# Sheet1.net
KiCad netlist of a schematic drawn in Altium Designer
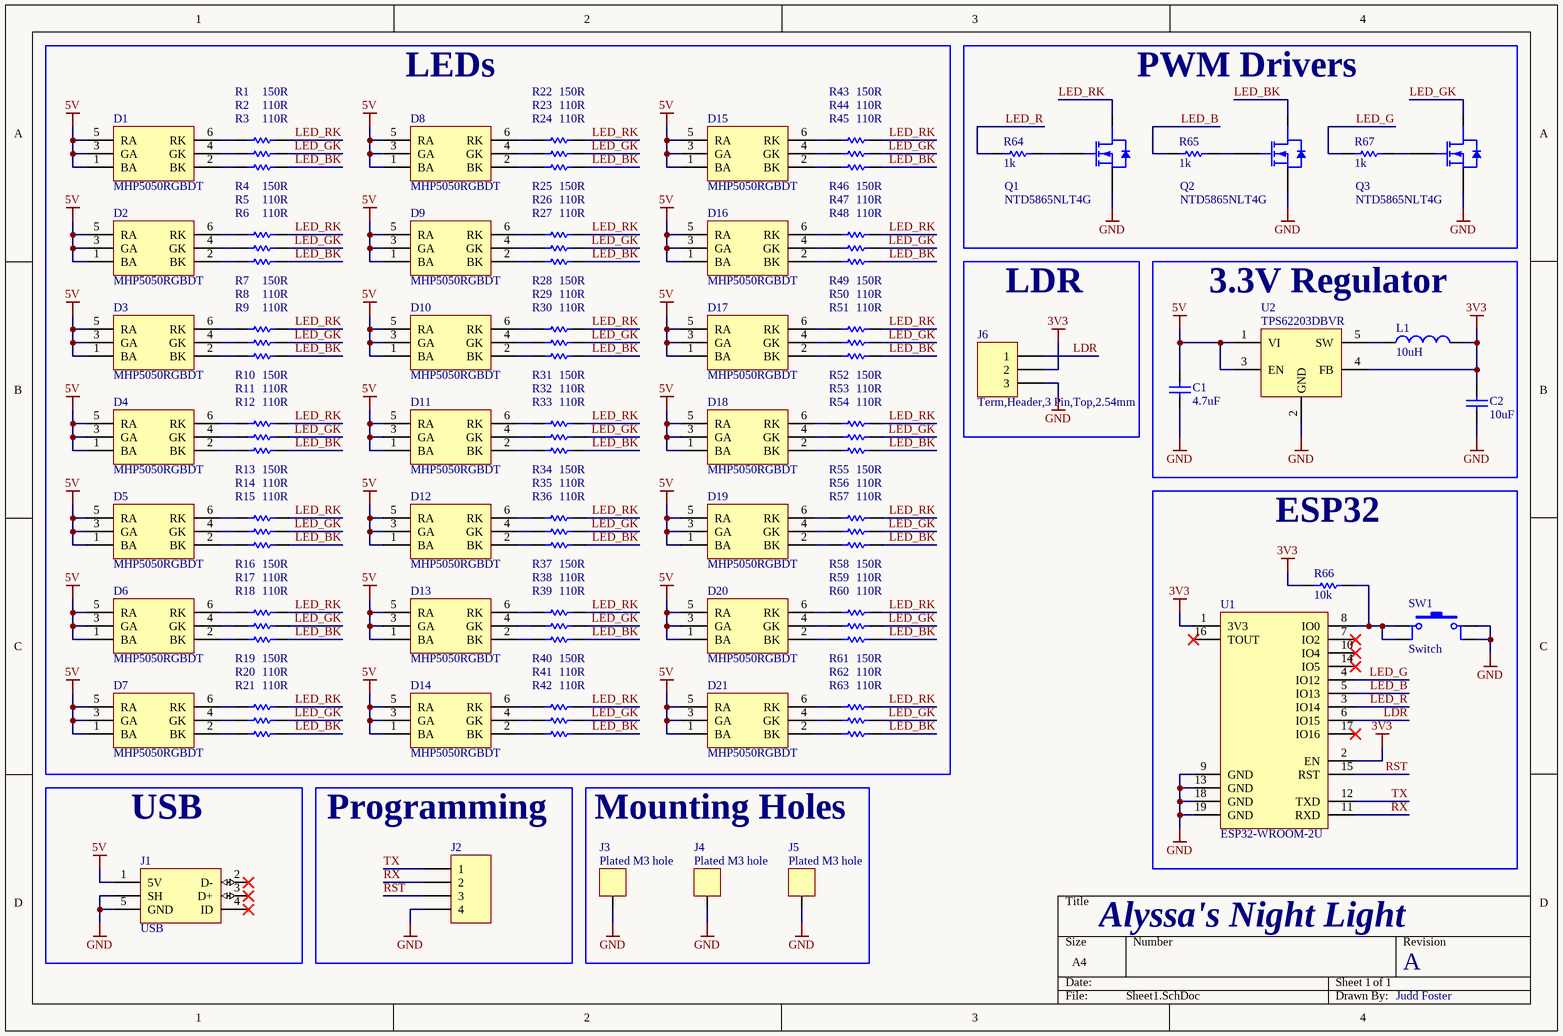
[diagram p0: Sheet1.SchDoc]

(export (version "E")
  (design (tool "Eeschema 10.0.6"))
  (components
    (comp (ref "C1")
      (value "4.7uF")
      (footprint "Cap,SMD,0805")
      (description "4.7µF ±10% 16V Ceramic Capacitor X7R 0805 (2012 Metric)")
      (fields
        (field (name "VENDOR PART NUMBER") "490-14466-1-ND")
        (field (name "MANUFACTURER") "KEMET")
        (field (name "CREATEDBY") "Judd Foster")
      )
      (libsource (lib "symbols") (part "CAP,Cer,4.7uF,16VDC,X7R,0805"))
    )
    (comp (ref "C2")
      (value "10uF")
      (footprint "Cap,SMD,0805")
      (description "CAP CER 10UF 10V X5R 0805")
      (fields
        (field (name "VENDOR PART NUMBER") "399-4925-1-ND")
        (field (name "MANUFACTURER") "KEMET")
        (field (name "CREATEDBY") "Judd Foster")
      )
      (libsource (lib "symbols") (part "CAP,Cer,10uF,10VDC,X5R,0805"))
    )
    (comp (ref "D1")
      (value "MHP5050RGBDT")
      (footprint "LED,RGB,SMD,5050")
      (description "SMD,5x5mm Light Emitting Diodes (LED) RoHS")
      (fields
        (field (name "MANUFACTURER") "MEIHUA")
        (field (name "VENDOR PART NUMBER") "C409780")
        (field (name "CREATEDBY") "Judd Foster")
      )
      (libsource (lib "symbols") (part "LED,Tri-Color,RGB,SMD,5050"))
    )
    (comp (ref "D2")
      (value "MHP5050RGBDT")
      (footprint "LED,RGB,SMD,5050")
      (description "SMD,5x5mm Light Emitting Diodes (LED) RoHS")
      (fields
        (field (name "MANUFACTURER") "MEIHUA")
        (field (name "VENDOR PART NUMBER") "C409780")
        (field (name "CREATEDBY") "Judd Foster")
      )
      (libsource (lib "symbols") (part "LED,Tri-Color,RGB,SMD,5050"))
    )
    (comp (ref "D3")
      (value "MHP5050RGBDT")
      (footprint "LED,RGB,SMD,5050")
      (description "SMD,5x5mm Light Emitting Diodes (LED) RoHS")
      (fields
        (field (name "MANUFACTURER") "MEIHUA")
        (field (name "VENDOR PART NUMBER") "C409780")
        (field (name "CREATEDBY") "Judd Foster")
      )
      (libsource (lib "symbols") (part "LED,Tri-Color,RGB,SMD,5050"))
    )
    (comp (ref "D4")
      (value "MHP5050RGBDT")
      (footprint "LED,RGB,SMD,5050")
      (description "SMD,5x5mm Light Emitting Diodes (LED) RoHS")
      (fields
        (field (name "MANUFACTURER") "MEIHUA")
        (field (name "VENDOR PART NUMBER") "C409780")
        (field (name "CREATEDBY") "Judd Foster")
      )
      (libsource (lib "symbols") (part "LED,Tri-Color,RGB,SMD,5050"))
    )
    (comp (ref "D5")
      (value "MHP5050RGBDT")
      (footprint "LED,RGB,SMD,5050")
      (description "SMD,5x5mm Light Emitting Diodes (LED) RoHS")
      (fields
        (field (name "MANUFACTURER") "MEIHUA")
        (field (name "VENDOR PART NUMBER") "C409780")
        (field (name "CREATEDBY") "Judd Foster")
      )
      (libsource (lib "symbols") (part "LED,Tri-Color,RGB,SMD,5050"))
    )
    (comp (ref "D6")
      (value "MHP5050RGBDT")
      (footprint "LED,RGB,SMD,5050")
      (description "SMD,5x5mm Light Emitting Diodes (LED) RoHS")
      (fields
        (field (name "MANUFACTURER") "MEIHUA")
        (field (name "VENDOR PART NUMBER") "C409780")
        (field (name "CREATEDBY") "Judd Foster")
      )
      (libsource (lib "symbols") (part "LED,Tri-Color,RGB,SMD,5050"))
    )
    (comp (ref "D7")
      (value "MHP5050RGBDT")
      (footprint "LED,RGB,SMD,5050")
      (description "SMD,5x5mm Light Emitting Diodes (LED) RoHS")
      (fields
        (field (name "MANUFACTURER") "MEIHUA")
        (field (name "VENDOR PART NUMBER") "C409780")
        (field (name "CREATEDBY") "Judd Foster")
      )
      (libsource (lib "symbols") (part "LED,Tri-Color,RGB,SMD,5050"))
    )
    (comp (ref "D8")
      (value "MHP5050RGBDT")
      (footprint "LED,RGB,SMD,5050")
      (description "SMD,5x5mm Light Emitting Diodes (LED) RoHS")
      (fields
        (field (name "MANUFACTURER") "MEIHUA")
        (field (name "VENDOR PART NUMBER") "C409780")
        (field (name "CREATEDBY") "Judd Foster")
      )
      (libsource (lib "symbols") (part "LED,Tri-Color,RGB,SMD,5050"))
    )
    (comp (ref "D9")
      (value "MHP5050RGBDT")
      (footprint "LED,RGB,SMD,5050")
      (description "SMD,5x5mm Light Emitting Diodes (LED) RoHS")
      (fields
        (field (name "MANUFACTURER") "MEIHUA")
        (field (name "VENDOR PART NUMBER") "C409780")
        (field (name "CREATEDBY") "Judd Foster")
      )
      (libsource (lib "symbols") (part "LED,Tri-Color,RGB,SMD,5050"))
    )
    (comp (ref "D10")
      (value "MHP5050RGBDT")
      (footprint "LED,RGB,SMD,5050")
      (description "SMD,5x5mm Light Emitting Diodes (LED) RoHS")
      (fields
        (field (name "MANUFACTURER") "MEIHUA")
        (field (name "VENDOR PART NUMBER") "C409780")
        (field (name "CREATEDBY") "Judd Foster")
      )
      (libsource (lib "symbols") (part "LED,Tri-Color,RGB,SMD,5050"))
    )
    (comp (ref "D11")
      (value "MHP5050RGBDT")
      (footprint "LED,RGB,SMD,5050")
      (description "SMD,5x5mm Light Emitting Diodes (LED) RoHS")
      (fields
        (field (name "MANUFACTURER") "MEIHUA")
        (field (name "VENDOR PART NUMBER") "C409780")
        (field (name "CREATEDBY") "Judd Foster")
      )
      (libsource (lib "symbols") (part "LED,Tri-Color,RGB,SMD,5050"))
    )
    (comp (ref "D12")
      (value "MHP5050RGBDT")
      (footprint "LED,RGB,SMD,5050")
      (description "SMD,5x5mm Light Emitting Diodes (LED) RoHS")
      (fields
        (field (name "MANUFACTURER") "MEIHUA")
        (field (name "VENDOR PART NUMBER") "C409780")
        (field (name "CREATEDBY") "Judd Foster")
      )
      (libsource (lib "symbols") (part "LED,Tri-Color,RGB,SMD,5050"))
    )
    (comp (ref "D13")
      (value "MHP5050RGBDT")
      (footprint "LED,RGB,SMD,5050")
      (description "SMD,5x5mm Light Emitting Diodes (LED) RoHS")
      (fields
        (field (name "MANUFACTURER") "MEIHUA")
        (field (name "VENDOR PART NUMBER") "C409780")
        (field (name "CREATEDBY") "Judd Foster")
      )
      (libsource (lib "symbols") (part "LED,Tri-Color,RGB,SMD,5050"))
    )
    (comp (ref "D14")
      (value "MHP5050RGBDT")
      (footprint "LED,RGB,SMD,5050")
      (description "SMD,5x5mm Light Emitting Diodes (LED) RoHS")
      (fields
        (field (name "MANUFACTURER") "MEIHUA")
        (field (name "VENDOR PART NUMBER") "C409780")
        (field (name "CREATEDBY") "Judd Foster")
      )
      (libsource (lib "symbols") (part "LED,Tri-Color,RGB,SMD,5050"))
    )
    (comp (ref "D15")
      (value "MHP5050RGBDT")
      (footprint "LED,RGB,SMD,5050")
      (description "SMD,5x5mm Light Emitting Diodes (LED) RoHS")
      (fields
        (field (name "MANUFACTURER") "MEIHUA")
        (field (name "VENDOR PART NUMBER") "C409780")
        (field (name "CREATEDBY") "Judd Foster")
      )
      (libsource (lib "symbols") (part "LED,Tri-Color,RGB,SMD,5050"))
    )
    (comp (ref "D16")
      (value "MHP5050RGBDT")
      (footprint "LED,RGB,SMD,5050")
      (description "SMD,5x5mm Light Emitting Diodes (LED) RoHS")
      (fields
        (field (name "MANUFACTURER") "MEIHUA")
        (field (name "VENDOR PART NUMBER") "C409780")
        (field (name "CREATEDBY") "Judd Foster")
      )
      (libsource (lib "symbols") (part "LED,Tri-Color,RGB,SMD,5050"))
    )
    (comp (ref "D17")
      (value "MHP5050RGBDT")
      (footprint "LED,RGB,SMD,5050")
      (description "SMD,5x5mm Light Emitting Diodes (LED) RoHS")
      (fields
        (field (name "MANUFACTURER") "MEIHUA")
        (field (name "VENDOR PART NUMBER") "C409780")
        (field (name "CREATEDBY") "Judd Foster")
      )
      (libsource (lib "symbols") (part "LED,Tri-Color,RGB,SMD,5050"))
    )
    (comp (ref "D18")
      (value "MHP5050RGBDT")
      (footprint "LED,RGB,SMD,5050")
      (description "SMD,5x5mm Light Emitting Diodes (LED) RoHS")
      (fields
        (field (name "MANUFACTURER") "MEIHUA")
        (field (name "VENDOR PART NUMBER") "C409780")
        (field (name "CREATEDBY") "Judd Foster")
      )
      (libsource (lib "symbols") (part "LED,Tri-Color,RGB,SMD,5050"))
    )
    (comp (ref "D19")
      (value "MHP5050RGBDT")
      (footprint "LED,RGB,SMD,5050")
      (description "SMD,5x5mm Light Emitting Diodes (LED) RoHS")
      (fields
        (field (name "MANUFACTURER") "MEIHUA")
        (field (name "VENDOR PART NUMBER") "C409780")
        (field (name "CREATEDBY") "Judd Foster")
      )
      (libsource (lib "symbols") (part "LED,Tri-Color,RGB,SMD,5050"))
    )
    (comp (ref "D20")
      (value "MHP5050RGBDT")
      (footprint "LED,RGB,SMD,5050")
      (description "SMD,5x5mm Light Emitting Diodes (LED) RoHS")
      (fields
        (field (name "MANUFACTURER") "MEIHUA")
        (field (name "VENDOR PART NUMBER") "C409780")
        (field (name "CREATEDBY") "Judd Foster")
      )
      (libsource (lib "symbols") (part "LED,Tri-Color,RGB,SMD,5050"))
    )
    (comp (ref "D21")
      (value "MHP5050RGBDT")
      (footprint "LED,RGB,SMD,5050")
      (description "SMD,5x5mm Light Emitting Diodes (LED) RoHS")
      (fields
        (field (name "MANUFACTURER") "MEIHUA")
        (field (name "VENDOR PART NUMBER") "C409780")
        (field (name "CREATEDBY") "Judd Foster")
      )
      (libsource (lib "symbols") (part "LED,Tri-Color,RGB,SMD,5050"))
    )
    (comp (ref "J1")
      (value "USB")
      (footprint "Conn,USB,MicroB,SMD")
      (description "USB - micro B USB 2.0 Receptacle Connector 5 Position Surface Mount, Right Angle; Through Hole")
      (fields
        (field (name "MANUFACTURER") "Amphenol ICC (FCI)")
        (field (name "MANUFACTURER PART NUMBER") "10118193-0001LF")
        (field (name "CREATEDBY") "Judd Foster")
      )
      (libsource (lib "symbols") (part "Conn,USB.Micro_B,SMD"))
    )
    (comp (ref "J2")
      (value "Term,Header,4 Pin,Top,2.54mm")
      (footprint "Term,Header,4Pin,2.54mm")
      (description "Connector Header Through Hole 4 position 0.100\" (2.54mm)")
      (fields
        (field (name "VENDOR PART NUMBER") "609-10082627-404HLF-ND")
        (field (name "MANUFACTURER") "Amphenol ICC (FCI)")
        (field (name "CREATED BY") "Judd Foster")
      )
      (libsource (lib "symbols") (part "Term,Header,4 Pin,Top,2.54mm"))
    )
    (comp (ref "J3")
      (value "Plated M3 hole")
      (footprint "HOLE,M3,3mm,PLATED")
      (description "3.5mm Drill, 7.4mm Pad, PTH")
      (fields (field (name "CREATEDBY") "Judd Foster"))
      (libsource (lib "symbols") (part "Mech,Hole,M3,3mm,Plated"))
    )
    (comp (ref "J4")
      (value "Plated M3 hole")
      (footprint "HOLE,M3,3mm,PLATED")
      (description "3.5mm Drill, 7.4mm Pad, PTH")
      (fields (field (name "CREATEDBY") "Judd Foster"))
      (libsource (lib "symbols") (part "Mech,Hole,M3,3mm,Plated"))
    )
    (comp (ref "J5")
      (value "Plated M3 hole")
      (footprint "HOLE,M3,3mm,PLATED")
      (description "3.5mm Drill, 7.4mm Pad, PTH")
      (fields (field (name "CREATEDBY") "Judd Foster"))
      (libsource (lib "symbols") (part "Mech,Hole,M3,3mm,Plated"))
    )
    (comp (ref "J6")
      (value "Term,Header,3 Pin,Top,2.54mm")
      (footprint "Term,Header,3Pin,2.54mm")
      (description "CONN HEADER VERT 3POS 2.54MM")
      (fields
        (field (name "VENDOR PART NUMBER") "732-5316-ND")
        (field (name "MANUFACTURER") "Würth Elektronik")
        (field (name "CREATED BY") "Judd Foster")
      )
      (libsource (lib "symbols") (part "Term,Header,3 Pin,Top,2.54mm"))
    )
    (comp (ref "L1")
      (value "10uH")
      (footprint "IND,Wirewound,4x4,SMD")
      (description "FIXED IND 10UH 1.17A 160 MOHM")
      (fields
        (field (name "VENDOR PART NUMBER") "‎490-5330-1-ND‎")
        (field (name "MANUFACTURER") "Murata Electronics")
        (field (name "CREATEDBY") "Judd Foster")
      )
      (libsource (lib "symbols") (part "IND,10uH,1.17A,Wirewound,SMD"))
    )
    (comp (ref "Q1")
      (value "NTD5865NLT4G")
      (footprint "DPAK3 (TO-252 3 Lead)")
      (description "MOSFET N-CH 60V 46A DPAK")
      (fields
        (field (name "MANUFACTURER") "ON Semiconductor")
        (field (name "VENDOR PART NUMBER") "NTD5865NLT4GOSCT-ND")
        (field (name "CREATEDBY") "Judd Foster")
      )
      (libsource (lib "symbols") (part "MOSFET,N Ch,60V,46A"))
    )
    (comp (ref "Q2")
      (value "NTD5865NLT4G")
      (footprint "DPAK3 (TO-252 3 Lead)")
      (description "MOSFET N-CH 60V 46A DPAK")
      (fields
        (field (name "MANUFACTURER") "ON Semiconductor")
        (field (name "VENDOR PART NUMBER") "NTD5865NLT4GOSCT-ND")
        (field (name "CREATEDBY") "Judd Foster")
      )
      (libsource (lib "symbols") (part "MOSFET,N Ch,60V,46A"))
    )
    (comp (ref "Q3")
      (value "NTD5865NLT4G")
      (footprint "DPAK3 (TO-252 3 Lead)")
      (description "MOSFET N-CH 60V 46A DPAK")
      (fields
        (field (name "MANUFACTURER") "ON Semiconductor")
        (field (name "VENDOR PART NUMBER") "NTD5865NLT4GOSCT-ND")
        (field (name "CREATEDBY") "Judd Foster")
      )
      (libsource (lib "symbols") (part "MOSFET,N Ch,60V,46A"))
    )
    (comp (ref "R1")
      (value "150R")
      (footprint "RES,0603")
      (fields
        (field (name "MANUFACTURER") "TE Connectivity Passive Product")
        (field (name "MANUFACTURER PART NUMBER") "CRGCQ0603F150R")
        (field (name "VENDOR PART NUMBER") "A129678CT-ND")
        (field (name "CREATEDBY") "Judd Foster")
      )
      (libsource (lib "symbols") (part "RES,150R,1%,0.1W,0603"))
    )
    (comp (ref "R2")
      (value "110R")
      (footprint "RES,0603")
      (description "110 Ohms ±0.5% 0.063W, 1/16W Chip Resistor 0603 (1608 Metric)  Thin Film")
      (fields
        (field (name "MANUFACTURER") "Susumu")
        (field (name "MANUFACTURER PART NUMBER") "RR0816P-111-D")
        (field (name "CREATEDBY") "Judd Foster")
      )
      (libsource (lib "symbols") (part "RES,110R,1%,0.1W,0603"))
    )
    (comp (ref "R3")
      (value "110R")
      (footprint "RES,0603")
      (description "110 Ohms ±0.5% 0.063W, 1/16W Chip Resistor 0603 (1608 Metric)  Thin Film")
      (fields
        (field (name "MANUFACTURER") "Susumu")
        (field (name "MANUFACTURER PART NUMBER") "RR0816P-111-D")
        (field (name "CREATEDBY") "Judd Foster")
      )
      (libsource (lib "symbols") (part "RES,110R,1%,0.1W,0603"))
    )
    (comp (ref "R4")
      (value "150R")
      (footprint "RES,0603")
      (fields
        (field (name "MANUFACTURER") "TE Connectivity Passive Product")
        (field (name "MANUFACTURER PART NUMBER") "CRGCQ0603F150R")
        (field (name "VENDOR PART NUMBER") "A129678CT-ND")
        (field (name "CREATEDBY") "Judd Foster")
      )
      (libsource (lib "symbols") (part "RES,150R,1%,0.1W,0603"))
    )
    (comp (ref "R5")
      (value "110R")
      (footprint "RES,0603")
      (description "110 Ohms ±0.5% 0.063W, 1/16W Chip Resistor 0603 (1608 Metric)  Thin Film")
      (fields
        (field (name "MANUFACTURER") "Susumu")
        (field (name "MANUFACTURER PART NUMBER") "RR0816P-111-D")
        (field (name "CREATEDBY") "Judd Foster")
      )
      (libsource (lib "symbols") (part "RES,110R,1%,0.1W,0603"))
    )
    (comp (ref "R6")
      (value "110R")
      (footprint "RES,0603")
      (description "110 Ohms ±0.5% 0.063W, 1/16W Chip Resistor 0603 (1608 Metric)  Thin Film")
      (fields
        (field (name "MANUFACTURER") "Susumu")
        (field (name "MANUFACTURER PART NUMBER") "RR0816P-111-D")
        (field (name "CREATEDBY") "Judd Foster")
      )
      (libsource (lib "symbols") (part "RES,110R,1%,0.1W,0603"))
    )
    (comp (ref "R7")
      (value "150R")
      (footprint "RES,0603")
      (fields
        (field (name "MANUFACTURER") "TE Connectivity Passive Product")
        (field (name "MANUFACTURER PART NUMBER") "CRGCQ0603F150R")
        (field (name "VENDOR PART NUMBER") "A129678CT-ND")
        (field (name "CREATEDBY") "Judd Foster")
      )
      (libsource (lib "symbols") (part "RES,150R,1%,0.1W,0603"))
    )
    (comp (ref "R8")
      (value "110R")
      (footprint "RES,0603")
      (description "110 Ohms ±0.5% 0.063W, 1/16W Chip Resistor 0603 (1608 Metric)  Thin Film")
      (fields
        (field (name "MANUFACTURER") "Susumu")
        (field (name "MANUFACTURER PART NUMBER") "RR0816P-111-D")
        (field (name "CREATEDBY") "Judd Foster")
      )
      (libsource (lib "symbols") (part "RES,110R,1%,0.1W,0603"))
    )
    (comp (ref "R9")
      (value "110R")
      (footprint "RES,0603")
      (description "110 Ohms ±0.5% 0.063W, 1/16W Chip Resistor 0603 (1608 Metric)  Thin Film")
      (fields
        (field (name "MANUFACTURER") "Susumu")
        (field (name "MANUFACTURER PART NUMBER") "RR0816P-111-D")
        (field (name "CREATEDBY") "Judd Foster")
      )
      (libsource (lib "symbols") (part "RES,110R,1%,0.1W,0603"))
    )
    (comp (ref "R10")
      (value "150R")
      (footprint "RES,0603")
      (fields
        (field (name "MANUFACTURER") "TE Connectivity Passive Product")
        (field (name "MANUFACTURER PART NUMBER") "CRGCQ0603F150R")
        (field (name "VENDOR PART NUMBER") "A129678CT-ND")
        (field (name "CREATEDBY") "Judd Foster")
      )
      (libsource (lib "symbols") (part "RES,150R,1%,0.1W,0603"))
    )
    (comp (ref "R11")
      (value "110R")
      (footprint "RES,0603")
      (description "110 Ohms ±0.5% 0.063W, 1/16W Chip Resistor 0603 (1608 Metric)  Thin Film")
      (fields
        (field (name "MANUFACTURER") "Susumu")
        (field (name "MANUFACTURER PART NUMBER") "RR0816P-111-D")
        (field (name "CREATEDBY") "Judd Foster")
      )
      (libsource (lib "symbols") (part "RES,110R,1%,0.1W,0603"))
    )
    (comp (ref "R12")
      (value "110R")
      (footprint "RES,0603")
      (description "110 Ohms ±0.5% 0.063W, 1/16W Chip Resistor 0603 (1608 Metric)  Thin Film")
      (fields
        (field (name "MANUFACTURER") "Susumu")
        (field (name "MANUFACTURER PART NUMBER") "RR0816P-111-D")
        (field (name "CREATEDBY") "Judd Foster")
      )
      (libsource (lib "symbols") (part "RES,110R,1%,0.1W,0603"))
    )
    (comp (ref "R13")
      (value "150R")
      (footprint "RES,0603")
      (fields
        (field (name "MANUFACTURER") "TE Connectivity Passive Product")
        (field (name "MANUFACTURER PART NUMBER") "CRGCQ0603F150R")
        (field (name "VENDOR PART NUMBER") "A129678CT-ND")
        (field (name "CREATEDBY") "Judd Foster")
      )
      (libsource (lib "symbols") (part "RES,150R,1%,0.1W,0603"))
    )
    (comp (ref "R14")
      (value "110R")
      (footprint "RES,0603")
      (description "110 Ohms ±0.5% 0.063W, 1/16W Chip Resistor 0603 (1608 Metric)  Thin Film")
      (fields
        (field (name "MANUFACTURER") "Susumu")
        (field (name "MANUFACTURER PART NUMBER") "RR0816P-111-D")
        (field (name "CREATEDBY") "Judd Foster")
      )
      (libsource (lib "symbols") (part "RES,110R,1%,0.1W,0603"))
    )
    (comp (ref "R15")
      (value "110R")
      (footprint "RES,0603")
      (description "110 Ohms ±0.5% 0.063W, 1/16W Chip Resistor 0603 (1608 Metric)  Thin Film")
      (fields
        (field (name "MANUFACTURER") "Susumu")
        (field (name "MANUFACTURER PART NUMBER") "RR0816P-111-D")
        (field (name "CREATEDBY") "Judd Foster")
      )
      (libsource (lib "symbols") (part "RES,110R,1%,0.1W,0603"))
    )
    (comp (ref "R16")
      (value "150R")
      (footprint "RES,0603")
      (fields
        (field (name "MANUFACTURER") "TE Connectivity Passive Product")
        (field (name "MANUFACTURER PART NUMBER") "CRGCQ0603F150R")
        (field (name "VENDOR PART NUMBER") "A129678CT-ND")
        (field (name "CREATEDBY") "Judd Foster")
      )
      (libsource (lib "symbols") (part "RES,150R,1%,0.1W,0603"))
    )
    (comp (ref "R17")
      (value "110R")
      (footprint "RES,0603")
      (description "110 Ohms ±0.5% 0.063W, 1/16W Chip Resistor 0603 (1608 Metric)  Thin Film")
      (fields
        (field (name "MANUFACTURER") "Susumu")
        (field (name "MANUFACTURER PART NUMBER") "RR0816P-111-D")
        (field (name "CREATEDBY") "Judd Foster")
      )
      (libsource (lib "symbols") (part "RES,110R,1%,0.1W,0603"))
    )
    (comp (ref "R18")
      (value "110R")
      (footprint "RES,0603")
      (description "110 Ohms ±0.5% 0.063W, 1/16W Chip Resistor 0603 (1608 Metric)  Thin Film")
      (fields
        (field (name "MANUFACTURER") "Susumu")
        (field (name "MANUFACTURER PART NUMBER") "RR0816P-111-D")
        (field (name "CREATEDBY") "Judd Foster")
      )
      (libsource (lib "symbols") (part "RES,110R,1%,0.1W,0603"))
    )
    (comp (ref "R19")
      (value "150R")
      (footprint "RES,0603")
      (fields
        (field (name "MANUFACTURER") "TE Connectivity Passive Product")
        (field (name "MANUFACTURER PART NUMBER") "CRGCQ0603F150R")
        (field (name "VENDOR PART NUMBER") "A129678CT-ND")
        (field (name "CREATEDBY") "Judd Foster")
      )
      (libsource (lib "symbols") (part "RES,150R,1%,0.1W,0603"))
    )
    (comp (ref "R20")
      (value "110R")
      (footprint "RES,0603")
      (description "110 Ohms ±0.5% 0.063W, 1/16W Chip Resistor 0603 (1608 Metric)  Thin Film")
      (fields
        (field (name "MANUFACTURER") "Susumu")
        (field (name "MANUFACTURER PART NUMBER") "RR0816P-111-D")
        (field (name "CREATEDBY") "Judd Foster")
      )
      (libsource (lib "symbols") (part "RES,110R,1%,0.1W,0603"))
    )
    (comp (ref "R21")
      (value "110R")
      (footprint "RES,0603")
      (description "110 Ohms ±0.5% 0.063W, 1/16W Chip Resistor 0603 (1608 Metric)  Thin Film")
      (fields
        (field (name "MANUFACTURER") "Susumu")
        (field (name "MANUFACTURER PART NUMBER") "RR0816P-111-D")
        (field (name "CREATEDBY") "Judd Foster")
      )
      (libsource (lib "symbols") (part "RES,110R,1%,0.1W,0603"))
    )
    (comp (ref "R22")
      (value "150R")
      (footprint "RES,0603")
      (fields
        (field (name "MANUFACTURER") "TE Connectivity Passive Product")
        (field (name "MANUFACTURER PART NUMBER") "CRGCQ0603F150R")
        (field (name "VENDOR PART NUMBER") "A129678CT-ND")
        (field (name "CREATEDBY") "Judd Foster")
      )
      (libsource (lib "symbols") (part "RES,150R,1%,0.1W,0603"))
    )
    (comp (ref "R23")
      (value "110R")
      (footprint "RES,0603")
      (description "110 Ohms ±0.5% 0.063W, 1/16W Chip Resistor 0603 (1608 Metric)  Thin Film")
      (fields
        (field (name "MANUFACTURER") "Susumu")
        (field (name "MANUFACTURER PART NUMBER") "RR0816P-111-D")
        (field (name "CREATEDBY") "Judd Foster")
      )
      (libsource (lib "symbols") (part "RES,110R,1%,0.1W,0603"))
    )
    (comp (ref "R24")
      (value "110R")
      (footprint "RES,0603")
      (description "110 Ohms ±0.5% 0.063W, 1/16W Chip Resistor 0603 (1608 Metric)  Thin Film")
      (fields
        (field (name "MANUFACTURER") "Susumu")
        (field (name "MANUFACTURER PART NUMBER") "RR0816P-111-D")
        (field (name "CREATEDBY") "Judd Foster")
      )
      (libsource (lib "symbols") (part "RES,110R,1%,0.1W,0603"))
    )
    (comp (ref "R25")
      (value "150R")
      (footprint "RES,0603")
      (fields
        (field (name "MANUFACTURER") "TE Connectivity Passive Product")
        (field (name "MANUFACTURER PART NUMBER") "CRGCQ0603F150R")
        (field (name "VENDOR PART NUMBER") "A129678CT-ND")
        (field (name "CREATEDBY") "Judd Foster")
      )
      (libsource (lib "symbols") (part "RES,150R,1%,0.1W,0603"))
    )
    (comp (ref "R26")
      (value "110R")
      (footprint "RES,0603")
      (description "110 Ohms ±0.5% 0.063W, 1/16W Chip Resistor 0603 (1608 Metric)  Thin Film")
      (fields
        (field (name "MANUFACTURER") "Susumu")
        (field (name "MANUFACTURER PART NUMBER") "RR0816P-111-D")
        (field (name "CREATEDBY") "Judd Foster")
      )
      (libsource (lib "symbols") (part "RES,110R,1%,0.1W,0603"))
    )
    (comp (ref "R27")
      (value "110R")
      (footprint "RES,0603")
      (description "110 Ohms ±0.5% 0.063W, 1/16W Chip Resistor 0603 (1608 Metric)  Thin Film")
      (fields
        (field (name "MANUFACTURER") "Susumu")
        (field (name "MANUFACTURER PART NUMBER") "RR0816P-111-D")
        (field (name "CREATEDBY") "Judd Foster")
      )
      (libsource (lib "symbols") (part "RES,110R,1%,0.1W,0603"))
    )
    (comp (ref "R28")
      (value "150R")
      (footprint "RES,0603")
      (fields
        (field (name "MANUFACTURER") "TE Connectivity Passive Product")
        (field (name "MANUFACTURER PART NUMBER") "CRGCQ0603F150R")
        (field (name "VENDOR PART NUMBER") "A129678CT-ND")
        (field (name "CREATEDBY") "Judd Foster")
      )
      (libsource (lib "symbols") (part "RES,150R,1%,0.1W,0603"))
    )
    (comp (ref "R29")
      (value "110R")
      (footprint "RES,0603")
      (description "110 Ohms ±0.5% 0.063W, 1/16W Chip Resistor 0603 (1608 Metric)  Thin Film")
      (fields
        (field (name "MANUFACTURER") "Susumu")
        (field (name "MANUFACTURER PART NUMBER") "RR0816P-111-D")
        (field (name "CREATEDBY") "Judd Foster")
      )
      (libsource (lib "symbols") (part "RES,110R,1%,0.1W,0603"))
    )
    (comp (ref "R30")
      (value "110R")
      (footprint "RES,0603")
      (description "110 Ohms ±0.5% 0.063W, 1/16W Chip Resistor 0603 (1608 Metric)  Thin Film")
      (fields
        (field (name "MANUFACTURER") "Susumu")
        (field (name "MANUFACTURER PART NUMBER") "RR0816P-111-D")
        (field (name "CREATEDBY") "Judd Foster")
      )
      (libsource (lib "symbols") (part "RES,110R,1%,0.1W,0603"))
    )
    (comp (ref "R31")
      (value "150R")
      (footprint "RES,0603")
      (fields
        (field (name "MANUFACTURER") "TE Connectivity Passive Product")
        (field (name "MANUFACTURER PART NUMBER") "CRGCQ0603F150R")
        (field (name "VENDOR PART NUMBER") "A129678CT-ND")
        (field (name "CREATEDBY") "Judd Foster")
      )
      (libsource (lib "symbols") (part "RES,150R,1%,0.1W,0603"))
    )
    (comp (ref "R32")
      (value "110R")
      (footprint "RES,0603")
      (description "110 Ohms ±0.5% 0.063W, 1/16W Chip Resistor 0603 (1608 Metric)  Thin Film")
      (fields
        (field (name "MANUFACTURER") "Susumu")
        (field (name "MANUFACTURER PART NUMBER") "RR0816P-111-D")
        (field (name "CREATEDBY") "Judd Foster")
      )
      (libsource (lib "symbols") (part "RES,110R,1%,0.1W,0603"))
    )
    (comp (ref "R33")
      (value "110R")
      (footprint "RES,0603")
      (description "110 Ohms ±0.5% 0.063W, 1/16W Chip Resistor 0603 (1608 Metric)  Thin Film")
      (fields
        (field (name "MANUFACTURER") "Susumu")
        (field (name "MANUFACTURER PART NUMBER") "RR0816P-111-D")
        (field (name "CREATEDBY") "Judd Foster")
      )
      (libsource (lib "symbols") (part "RES,110R,1%,0.1W,0603"))
    )
    (comp (ref "R34")
      (value "150R")
      (footprint "RES,0603")
      (fields
        (field (name "MANUFACTURER") "TE Connectivity Passive Product")
        (field (name "MANUFACTURER PART NUMBER") "CRGCQ0603F150R")
        (field (name "VENDOR PART NUMBER") "A129678CT-ND")
        (field (name "CREATEDBY") "Judd Foster")
      )
      (libsource (lib "symbols") (part "RES,150R,1%,0.1W,0603"))
    )
    (comp (ref "R35")
      (value "110R")
      (footprint "RES,0603")
      (description "110 Ohms ±0.5% 0.063W, 1/16W Chip Resistor 0603 (1608 Metric)  Thin Film")
      (fields
        (field (name "MANUFACTURER") "Susumu")
        (field (name "MANUFACTURER PART NUMBER") "RR0816P-111-D")
        (field (name "CREATEDBY") "Judd Foster")
      )
      (libsource (lib "symbols") (part "RES,110R,1%,0.1W,0603"))
    )
    (comp (ref "R36")
      (value "110R")
      (footprint "RES,0603")
      (description "110 Ohms ±0.5% 0.063W, 1/16W Chip Resistor 0603 (1608 Metric)  Thin Film")
      (fields
        (field (name "MANUFACTURER") "Susumu")
        (field (name "MANUFACTURER PART NUMBER") "RR0816P-111-D")
        (field (name "CREATEDBY") "Judd Foster")
      )
      (libsource (lib "symbols") (part "RES,110R,1%,0.1W,0603"))
    )
    (comp (ref "R37")
      (value "150R")
      (footprint "RES,0603")
      (fields
        (field (name "MANUFACTURER") "TE Connectivity Passive Product")
        (field (name "MANUFACTURER PART NUMBER") "CRGCQ0603F150R")
        (field (name "VENDOR PART NUMBER") "A129678CT-ND")
        (field (name "CREATEDBY") "Judd Foster")
      )
      (libsource (lib "symbols") (part "RES,150R,1%,0.1W,0603"))
    )
    (comp (ref "R38")
      (value "110R")
      (footprint "RES,0603")
      (description "110 Ohms ±0.5% 0.063W, 1/16W Chip Resistor 0603 (1608 Metric)  Thin Film")
      (fields
        (field (name "MANUFACTURER") "Susumu")
        (field (name "MANUFACTURER PART NUMBER") "RR0816P-111-D")
        (field (name "CREATEDBY") "Judd Foster")
      )
      (libsource (lib "symbols") (part "RES,110R,1%,0.1W,0603"))
    )
    (comp (ref "R39")
      (value "110R")
      (footprint "RES,0603")
      (description "110 Ohms ±0.5% 0.063W, 1/16W Chip Resistor 0603 (1608 Metric)  Thin Film")
      (fields
        (field (name "MANUFACTURER") "Susumu")
        (field (name "MANUFACTURER PART NUMBER") "RR0816P-111-D")
        (field (name "CREATEDBY") "Judd Foster")
      )
      (libsource (lib "symbols") (part "RES,110R,1%,0.1W,0603"))
    )
    (comp (ref "R40")
      (value "150R")
      (footprint "RES,0603")
      (fields
        (field (name "MANUFACTURER") "TE Connectivity Passive Product")
        (field (name "MANUFACTURER PART NUMBER") "CRGCQ0603F150R")
        (field (name "VENDOR PART NUMBER") "A129678CT-ND")
        (field (name "CREATEDBY") "Judd Foster")
      )
      (libsource (lib "symbols") (part "RES,150R,1%,0.1W,0603"))
    )
    (comp (ref "R41")
      (value "110R")
      (footprint "RES,0603")
      (description "110 Ohms ±0.5% 0.063W, 1/16W Chip Resistor 0603 (1608 Metric)  Thin Film")
      (fields
        (field (name "MANUFACTURER") "Susumu")
        (field (name "MANUFACTURER PART NUMBER") "RR0816P-111-D")
        (field (name "CREATEDBY") "Judd Foster")
      )
      (libsource (lib "symbols") (part "RES,110R,1%,0.1W,0603"))
    )
    (comp (ref "R42")
      (value "110R")
      (footprint "RES,0603")
      (description "110 Ohms ±0.5% 0.063W, 1/16W Chip Resistor 0603 (1608 Metric)  Thin Film")
      (fields
        (field (name "MANUFACTURER") "Susumu")
        (field (name "MANUFACTURER PART NUMBER") "RR0816P-111-D")
        (field (name "CREATEDBY") "Judd Foster")
      )
      (libsource (lib "symbols") (part "RES,110R,1%,0.1W,0603"))
    )
    (comp (ref "R43")
      (value "150R")
      (footprint "RES,0603")
      (fields
        (field (name "MANUFACTURER") "TE Connectivity Passive Product")
        (field (name "MANUFACTURER PART NUMBER") "CRGCQ0603F150R")
        (field (name "VENDOR PART NUMBER") "A129678CT-ND")
        (field (name "CREATEDBY") "Judd Foster")
      )
      (libsource (lib "symbols") (part "RES,150R,1%,0.1W,0603"))
    )
    (comp (ref "R44")
      (value "110R")
      (footprint "RES,0603")
      (description "110 Ohms ±0.5% 0.063W, 1/16W Chip Resistor 0603 (1608 Metric)  Thin Film")
      (fields
        (field (name "MANUFACTURER") "Susumu")
        (field (name "MANUFACTURER PART NUMBER") "RR0816P-111-D")
        (field (name "CREATEDBY") "Judd Foster")
      )
      (libsource (lib "symbols") (part "RES,110R,1%,0.1W,0603"))
    )
    (comp (ref "R45")
      (value "110R")
      (footprint "RES,0603")
      (description "110 Ohms ±0.5% 0.063W, 1/16W Chip Resistor 0603 (1608 Metric)  Thin Film")
      (fields
        (field (name "MANUFACTURER") "Susumu")
        (field (name "MANUFACTURER PART NUMBER") "RR0816P-111-D")
        (field (name "CREATEDBY") "Judd Foster")
      )
      (libsource (lib "symbols") (part "RES,110R,1%,0.1W,0603"))
    )
    (comp (ref "R46")
      (value "150R")
      (footprint "RES,0603")
      (fields
        (field (name "MANUFACTURER") "TE Connectivity Passive Product")
        (field (name "MANUFACTURER PART NUMBER") "CRGCQ0603F150R")
        (field (name "VENDOR PART NUMBER") "A129678CT-ND")
        (field (name "CREATEDBY") "Judd Foster")
      )
      (libsource (lib "symbols") (part "RES,150R,1%,0.1W,0603"))
    )
    (comp (ref "R47")
      (value "110R")
      (footprint "RES,0603")
      (description "110 Ohms ±0.5% 0.063W, 1/16W Chip Resistor 0603 (1608 Metric)  Thin Film")
      (fields
        (field (name "MANUFACTURER") "Susumu")
        (field (name "MANUFACTURER PART NUMBER") "RR0816P-111-D")
        (field (name "CREATEDBY") "Judd Foster")
      )
      (libsource (lib "symbols") (part "RES,110R,1%,0.1W,0603"))
    )
    (comp (ref "R48")
      (value "110R")
      (footprint "RES,0603")
      (description "110 Ohms ±0.5% 0.063W, 1/16W Chip Resistor 0603 (1608 Metric)  Thin Film")
      (fields
        (field (name "MANUFACTURER") "Susumu")
        (field (name "MANUFACTURER PART NUMBER") "RR0816P-111-D")
        (field (name "CREATEDBY") "Judd Foster")
      )
      (libsource (lib "symbols") (part "RES,110R,1%,0.1W,0603"))
    )
    (comp (ref "R49")
      (value "150R")
      (footprint "RES,0603")
      (fields
        (field (name "MANUFACTURER") "TE Connectivity Passive Product")
        (field (name "MANUFACTURER PART NUMBER") "CRGCQ0603F150R")
        (field (name "VENDOR PART NUMBER") "A129678CT-ND")
        (field (name "CREATEDBY") "Judd Foster")
      )
      (libsource (lib "symbols") (part "RES,150R,1%,0.1W,0603"))
    )
    (comp (ref "R50")
      (value "110R")
      (footprint "RES,0603")
      (description "110 Ohms ±0.5% 0.063W, 1/16W Chip Resistor 0603 (1608 Metric)  Thin Film")
      (fields
        (field (name "MANUFACTURER") "Susumu")
        (field (name "MANUFACTURER PART NUMBER") "RR0816P-111-D")
        (field (name "CREATEDBY") "Judd Foster")
      )
      (libsource (lib "symbols") (part "RES,110R,1%,0.1W,0603"))
    )
    (comp (ref "R51")
      (value "110R")
      (footprint "RES,0603")
      (description "110 Ohms ±0.5% 0.063W, 1/16W Chip Resistor 0603 (1608 Metric)  Thin Film")
      (fields
        (field (name "MANUFACTURER") "Susumu")
        (field (name "MANUFACTURER PART NUMBER") "RR0816P-111-D")
        (field (name "CREATEDBY") "Judd Foster")
      )
      (libsource (lib "symbols") (part "RES,110R,1%,0.1W,0603"))
    )
    (comp (ref "R52")
      (value "150R")
      (footprint "RES,0603")
      (fields
        (field (name "MANUFACTURER") "TE Connectivity Passive Product")
        (field (name "MANUFACTURER PART NUMBER") "CRGCQ0603F150R")
        (field (name "VENDOR PART NUMBER") "A129678CT-ND")
        (field (name "CREATEDBY") "Judd Foster")
      )
      (libsource (lib "symbols") (part "RES,150R,1%,0.1W,0603"))
    )
    (comp (ref "R53")
      (value "110R")
      (footprint "RES,0603")
      (description "110 Ohms ±0.5% 0.063W, 1/16W Chip Resistor 0603 (1608 Metric)  Thin Film")
      (fields
        (field (name "MANUFACTURER") "Susumu")
        (field (name "MANUFACTURER PART NUMBER") "RR0816P-111-D")
        (field (name "CREATEDBY") "Judd Foster")
      )
      (libsource (lib "symbols") (part "RES,110R,1%,0.1W,0603"))
    )
    (comp (ref "R54")
      (value "110R")
      (footprint "RES,0603")
      (description "110 Ohms ±0.5% 0.063W, 1/16W Chip Resistor 0603 (1608 Metric)  Thin Film")
      (fields
        (field (name "MANUFACTURER") "Susumu")
        (field (name "MANUFACTURER PART NUMBER") "RR0816P-111-D")
        (field (name "CREATEDBY") "Judd Foster")
      )
      (libsource (lib "symbols") (part "RES,110R,1%,0.1W,0603"))
    )
    (comp (ref "R55")
      (value "150R")
      (footprint "RES,0603")
      (fields
        (field (name "MANUFACTURER") "TE Connectivity Passive Product")
        (field (name "MANUFACTURER PART NUMBER") "CRGCQ0603F150R")
        (field (name "VENDOR PART NUMBER") "A129678CT-ND")
        (field (name "CREATEDBY") "Judd Foster")
      )
      (libsource (lib "symbols") (part "RES,150R,1%,0.1W,0603"))
    )
    (comp (ref "R56")
      (value "110R")
      (footprint "RES,0603")
      (description "110 Ohms ±0.5% 0.063W, 1/16W Chip Resistor 0603 (1608 Metric)  Thin Film")
      (fields
        (field (name "MANUFACTURER") "Susumu")
        (field (name "MANUFACTURER PART NUMBER") "RR0816P-111-D")
        (field (name "CREATEDBY") "Judd Foster")
      )
      (libsource (lib "symbols") (part "RES,110R,1%,0.1W,0603"))
    )
    (comp (ref "R57")
      (value "110R")
      (footprint "RES,0603")
      (description "110 Ohms ±0.5% 0.063W, 1/16W Chip Resistor 0603 (1608 Metric)  Thin Film")
      (fields
        (field (name "MANUFACTURER") "Susumu")
        (field (name "MANUFACTURER PART NUMBER") "RR0816P-111-D")
        (field (name "CREATEDBY") "Judd Foster")
      )
      (libsource (lib "symbols") (part "RES,110R,1%,0.1W,0603"))
    )
    (comp (ref "R58")
      (value "150R")
      (footprint "RES,0603")
      (fields
        (field (name "MANUFACTURER") "TE Connectivity Passive Product")
        (field (name "MANUFACTURER PART NUMBER") "CRGCQ0603F150R")
        (field (name "VENDOR PART NUMBER") "A129678CT-ND")
        (field (name "CREATEDBY") "Judd Foster")
      )
      (libsource (lib "symbols") (part "RES,150R,1%,0.1W,0603"))
    )
    (comp (ref "R59")
      (value "110R")
      (footprint "RES,0603")
      (description "110 Ohms ±0.5% 0.063W, 1/16W Chip Resistor 0603 (1608 Metric)  Thin Film")
      (fields
        (field (name "MANUFACTURER") "Susumu")
        (field (name "MANUFACTURER PART NUMBER") "RR0816P-111-D")
        (field (name "CREATEDBY") "Judd Foster")
      )
      (libsource (lib "symbols") (part "RES,110R,1%,0.1W,0603"))
    )
    (comp (ref "R60")
      (value "110R")
      (footprint "RES,0603")
      (description "110 Ohms ±0.5% 0.063W, 1/16W Chip Resistor 0603 (1608 Metric)  Thin Film")
      (fields
        (field (name "MANUFACTURER") "Susumu")
        (field (name "MANUFACTURER PART NUMBER") "RR0816P-111-D")
        (field (name "CREATEDBY") "Judd Foster")
      )
      (libsource (lib "symbols") (part "RES,110R,1%,0.1W,0603"))
    )
    (comp (ref "R61")
      (value "150R")
      (footprint "RES,0603")
      (fields
        (field (name "MANUFACTURER") "TE Connectivity Passive Product")
        (field (name "MANUFACTURER PART NUMBER") "CRGCQ0603F150R")
        (field (name "VENDOR PART NUMBER") "A129678CT-ND")
        (field (name "CREATEDBY") "Judd Foster")
      )
      (libsource (lib "symbols") (part "RES,150R,1%,0.1W,0603"))
    )
    (comp (ref "R62")
      (value "110R")
      (footprint "RES,0603")
      (description "110 Ohms ±0.5% 0.063W, 1/16W Chip Resistor 0603 (1608 Metric)  Thin Film")
      (fields
        (field (name "MANUFACTURER") "Susumu")
        (field (name "MANUFACTURER PART NUMBER") "RR0816P-111-D")
        (field (name "CREATEDBY") "Judd Foster")
      )
      (libsource (lib "symbols") (part "RES,110R,1%,0.1W,0603"))
    )
    (comp (ref "R63")
      (value "110R")
      (footprint "RES,0603")
      (description "110 Ohms ±0.5% 0.063W, 1/16W Chip Resistor 0603 (1608 Metric)  Thin Film")
      (fields
        (field (name "MANUFACTURER") "Susumu")
        (field (name "MANUFACTURER PART NUMBER") "RR0816P-111-D")
        (field (name "CREATEDBY") "Judd Foster")
      )
      (libsource (lib "symbols") (part "RES,110R,1%,0.1W,0603"))
    )
    (comp (ref "R64")
      (value "1k")
      (footprint "RES,0603")
      (description "RES SMD 1K OHM 1% 1/10W 0603")
      (fields
        (field (name "MANUFACTURER") "Yageo")
        (field (name "MANUFACTURER PART NUMBER") "RC0603FR-071KL")
        (field (name "CREATEDBY") "Judd Foster")
      )
      (libsource (lib "symbols") (part "RES,1k,1%,0.1W,0603"))
    )
    (comp (ref "R65")
      (value "1k")
      (footprint "RES,0603")
      (description "RES SMD 1K OHM 1% 1/10W 0603")
      (fields
        (field (name "MANUFACTURER") "Yageo")
        (field (name "MANUFACTURER PART NUMBER") "RC0603FR-071KL")
        (field (name "CREATEDBY") "Judd Foster")
      )
      (libsource (lib "symbols") (part "RES,1k,1%,0.1W,0603"))
    )
    (comp (ref "R66")
      (value "10k")
      (footprint "RES,0603")
      (description "RES SMD 10K OHM 1% 1/10W 0603")
      (fields
        (field (name "MANUFACTURER") "Yageo")
        (field (name "MANUFACTURER PART NUMBER") "RC0603FR-0710KL")
        (field (name "CREATEDBY") "Judd Foster")
      )
      (libsource (lib "symbols") (part "RES,10k,1%,0.1W,0603"))
    )
    (comp (ref "R67")
      (value "1k")
      (footprint "RES,0603")
      (description "RES SMD 1K OHM 1% 1/10W 0603")
      (fields
        (field (name "MANUFACTURER") "Yageo")
        (field (name "MANUFACTURER PART NUMBER") "RC0603FR-071KL")
        (field (name "CREATEDBY") "Judd Foster")
      )
      (libsource (lib "symbols") (part "RES,1k,1%,0.1W,0603"))
    )
    (comp (ref "SW1")
      (value "Switch")
      (footprint "Switch,Tactile,SPST-NO,SMD")
      (description "Tactile Switch SPST-NO Top Actuated Surface Mount")
      (fields
        (field (name "MANUFACTURER") "C&K")
        (field (name "MANUFACTURER PART NUMBER") "PTS645SK43SMTR92 LFS")
        (field (name "CREATEDBY") "Judd Foster")
      )
      (libsource (lib "symbols") (part "Switch,Tactile,SPST-NO,SMD,H4.3"))
    )
    (comp (ref "U1")
      (value "ESP32-WROOM-2U")
      (footprint "ESP32-WROOM-02U")
      (description "WiFi 802.11b/g/n Transceiver Module 2.4GHz ~ 2.5GHz Integrated, Chip + IPEX Surface Mount")
      (fields
        (field (name "MANUFACTURER") "Espressif Systems")
        (field (name "MANUFACTURER PART NUMBER") "ESP-WROOM-02U (4MB)")
        (field (name "CREATEDBY") "Judd Foster")
      )
      (libsource (lib "symbols") (part "ESP32-WROOM-2U"))
    )
    (comp (ref "U2")
      (value "TPS62203DBVR")
      (footprint "SOT23-5")
      (description "IC REG BUCK 3.3V 300MA SOT23-5")
      (fields
        (field (name "MANUFACTURER") "Texas Instruments")
        (field (name "VENDOR PART NUMBER") "296-39452-1-ND")
        (field (name "CREATEDBY") "Judd Foster")
      )
      (libsource (lib "symbols") (part "TPS62203DBVR"))
    )
  )
  (nets
    (net (code "1") (name "/LDR") (class "Default")
      (node (ref "J6") (pin "1") (pinfunction "1_1") (pintype "passive"))
      (node (ref "U1") (pin "6") (pinfunction "IO15_6") (pintype "passive"))
    )
    (net (code "2") (name "/LED_B") (class "Default")
      (node (ref "R65") (pin "1") (pinfunction "1_1") (pintype "passive"))
      (node (ref "U1") (pin "5") (pinfunction "IO13_5") (pintype "passive"))
    )
    (net (code "3") (name "/LED_BK") (class "Default")
      (node (ref "Q2") (pin "4") (pinfunction "D_4") (pintype "passive"))
      (node (ref "R12") (pin "2") (pinfunction "2_2") (pintype "passive"))
      (node (ref "R15") (pin "2") (pinfunction "2_2") (pintype "passive"))
      (node (ref "R18") (pin "2") (pinfunction "2_2") (pintype "passive"))
      (node (ref "R21") (pin "2") (pinfunction "2_2") (pintype "passive"))
      (node (ref "R24") (pin "2") (pinfunction "2_2") (pintype "passive"))
      (node (ref "R27") (pin "2") (pinfunction "2_2") (pintype "passive"))
      (node (ref "R3") (pin "2") (pinfunction "2_2") (pintype "passive"))
      (node (ref "R30") (pin "2") (pinfunction "2_2") (pintype "passive"))
      (node (ref "R33") (pin "2") (pinfunction "2_2") (pintype "passive"))
      (node (ref "R36") (pin "2") (pinfunction "2_2") (pintype "passive"))
      (node (ref "R39") (pin "2") (pinfunction "2_2") (pintype "passive"))
      (node (ref "R42") (pin "2") (pinfunction "2_2") (pintype "passive"))
      (node (ref "R45") (pin "2") (pinfunction "2_2") (pintype "passive"))
      (node (ref "R48") (pin "2") (pinfunction "2_2") (pintype "passive"))
      (node (ref "R51") (pin "2") (pinfunction "2_2") (pintype "passive"))
      (node (ref "R54") (pin "2") (pinfunction "2_2") (pintype "passive"))
      (node (ref "R57") (pin "2") (pinfunction "2_2") (pintype "passive"))
      (node (ref "R6") (pin "2") (pinfunction "2_2") (pintype "passive"))
      (node (ref "R60") (pin "2") (pinfunction "2_2") (pintype "passive"))
      (node (ref "R63") (pin "2") (pinfunction "2_2") (pintype "passive"))
      (node (ref "R9") (pin "2") (pinfunction "2_2") (pintype "passive"))
    )
    (net (code "4") (name "/LED_G") (class "Default")
      (node (ref "R67") (pin "1") (pinfunction "1_1") (pintype "passive"))
      (node (ref "U1") (pin "4") (pinfunction "IO12_4") (pintype "passive"))
    )
    (net (code "5") (name "/LED_GK") (class "Default")
      (node (ref "Q3") (pin "4") (pinfunction "D_4") (pintype "passive"))
      (node (ref "R11") (pin "2") (pinfunction "2_2") (pintype "passive"))
      (node (ref "R14") (pin "2") (pinfunction "2_2") (pintype "passive"))
      (node (ref "R17") (pin "2") (pinfunction "2_2") (pintype "passive"))
      (node (ref "R2") (pin "2") (pinfunction "2_2") (pintype "passive"))
      (node (ref "R20") (pin "2") (pinfunction "2_2") (pintype "passive"))
      (node (ref "R23") (pin "2") (pinfunction "2_2") (pintype "passive"))
      (node (ref "R26") (pin "2") (pinfunction "2_2") (pintype "passive"))
      (node (ref "R29") (pin "2") (pinfunction "2_2") (pintype "passive"))
      (node (ref "R32") (pin "2") (pinfunction "2_2") (pintype "passive"))
      (node (ref "R35") (pin "2") (pinfunction "2_2") (pintype "passive"))
      (node (ref "R38") (pin "2") (pinfunction "2_2") (pintype "passive"))
      (node (ref "R41") (pin "2") (pinfunction "2_2") (pintype "passive"))
      (node (ref "R44") (pin "2") (pinfunction "2_2") (pintype "passive"))
      (node (ref "R47") (pin "2") (pinfunction "2_2") (pintype "passive"))
      (node (ref "R5") (pin "2") (pinfunction "2_2") (pintype "passive"))
      (node (ref "R50") (pin "2") (pinfunction "2_2") (pintype "passive"))
      (node (ref "R53") (pin "2") (pinfunction "2_2") (pintype "passive"))
      (node (ref "R56") (pin "2") (pinfunction "2_2") (pintype "passive"))
      (node (ref "R59") (pin "2") (pinfunction "2_2") (pintype "passive"))
      (node (ref "R62") (pin "2") (pinfunction "2_2") (pintype "passive"))
      (node (ref "R8") (pin "2") (pinfunction "2_2") (pintype "passive"))
    )
    (net (code "6") (name "/LED_R") (class "Default")
      (node (ref "R64") (pin "1") (pinfunction "1_1") (pintype "passive"))
      (node (ref "U1") (pin "3") (pinfunction "IO14_3") (pintype "passive"))
    )
    (net (code "7") (name "/LED_RK") (class "Default")
      (node (ref "Q1") (pin "4") (pinfunction "D_4") (pintype "passive"))
      (node (ref "R1") (pin "2") (pinfunction "2_2") (pintype "passive"))
      (node (ref "R10") (pin "2") (pinfunction "2_2") (pintype "passive"))
      (node (ref "R13") (pin "2") (pinfunction "2_2") (pintype "passive"))
      (node (ref "R16") (pin "2") (pinfunction "2_2") (pintype "passive"))
      (node (ref "R19") (pin "2") (pinfunction "2_2") (pintype "passive"))
      (node (ref "R22") (pin "2") (pinfunction "2_2") (pintype "passive"))
      (node (ref "R25") (pin "2") (pinfunction "2_2") (pintype "passive"))
      (node (ref "R28") (pin "2") (pinfunction "2_2") (pintype "passive"))
      (node (ref "R31") (pin "2") (pinfunction "2_2") (pintype "passive"))
      (node (ref "R34") (pin "2") (pinfunction "2_2") (pintype "passive"))
      (node (ref "R37") (pin "2") (pinfunction "2_2") (pintype "passive"))
      (node (ref "R4") (pin "2") (pinfunction "2_2") (pintype "passive"))
      (node (ref "R40") (pin "2") (pinfunction "2_2") (pintype "passive"))
      (node (ref "R43") (pin "2") (pinfunction "2_2") (pintype "passive"))
      (node (ref "R46") (pin "2") (pinfunction "2_2") (pintype "passive"))
      (node (ref "R49") (pin "2") (pinfunction "2_2") (pintype "passive"))
      (node (ref "R52") (pin "2") (pinfunction "2_2") (pintype "passive"))
      (node (ref "R55") (pin "2") (pinfunction "2_2") (pintype "passive"))
      (node (ref "R58") (pin "2") (pinfunction "2_2") (pintype "passive"))
      (node (ref "R61") (pin "2") (pinfunction "2_2") (pintype "passive"))
      (node (ref "R7") (pin "2") (pinfunction "2_2") (pintype "passive"))
    )
    (net (code "8") (name "/RST") (class "Default")
      (node (ref "J2") (pin "3") (pinfunction "3_3") (pintype "passive"))
      (node (ref "U1") (pin "15") (pinfunction "RST_15") (pintype "passive"))
    )
    (net (code "9") (name "/RX") (class "Default")
      (node (ref "J2") (pin "2") (pinfunction "2_2") (pintype "passive"))
      (node (ref "U1") (pin "11") (pinfunction "RXD_11") (pintype "passive"))
    )
    (net (code "10") (name "/TX") (class "Default")
      (node (ref "J2") (pin "1") (pinfunction "1_1") (pintype "passive"))
      (node (ref "U1") (pin "12") (pinfunction "TXD_12") (pintype "passive"))
    )
    (net (code "11") (name "3V3") (class "Default")
      (node (ref "C2") (pin "2") (pinfunction "2_2") (pintype "passive"))
      (node (ref "J6") (pin "2") (pinfunction "2_2") (pintype "passive"))
      (node (ref "L1") (pin "2") (pinfunction "2_2") (pintype "passive"))
      (node (ref "R66") (pin "2") (pinfunction "2_2") (pintype "passive"))
      (node (ref "U1") (pin "1") (pinfunction "3V3_1") (pintype "passive"))
      (node (ref "U1") (pin "2") (pinfunction "EN_2") (pintype "passive"))
      (node (ref "U2") (pin "4") (pinfunction "FB_4") (pintype "passive"))
    )
    (net (code "12") (name "5V") (class "Default")
      (node (ref "C1") (pin "2") (pinfunction "2_2") (pintype "passive"))
      (node (ref "D1") (pin "1") (pinfunction "BA_1") (pintype "passive"))
      (node (ref "D1") (pin "3") (pinfunction "GA_3") (pintype "passive"))
      (node (ref "D1") (pin "5") (pinfunction "RA_5") (pintype "passive"))
      (node (ref "D10") (pin "1") (pinfunction "BA_1") (pintype "passive"))
      (node (ref "D10") (pin "3") (pinfunction "GA_3") (pintype "passive"))
      (node (ref "D10") (pin "5") (pinfunction "RA_5") (pintype "passive"))
      (node (ref "D11") (pin "1") (pinfunction "BA_1") (pintype "passive"))
      (node (ref "D11") (pin "3") (pinfunction "GA_3") (pintype "passive"))
      (node (ref "D11") (pin "5") (pinfunction "RA_5") (pintype "passive"))
      (node (ref "D12") (pin "1") (pinfunction "BA_1") (pintype "passive"))
      (node (ref "D12") (pin "3") (pinfunction "GA_3") (pintype "passive"))
      (node (ref "D12") (pin "5") (pinfunction "RA_5") (pintype "passive"))
      (node (ref "D13") (pin "1") (pinfunction "BA_1") (pintype "passive"))
      (node (ref "D13") (pin "3") (pinfunction "GA_3") (pintype "passive"))
      (node (ref "D13") (pin "5") (pinfunction "RA_5") (pintype "passive"))
      (node (ref "D14") (pin "1") (pinfunction "BA_1") (pintype "passive"))
      (node (ref "D14") (pin "3") (pinfunction "GA_3") (pintype "passive"))
      (node (ref "D14") (pin "5") (pinfunction "RA_5") (pintype "passive"))
      (node (ref "D15") (pin "1") (pinfunction "BA_1") (pintype "passive"))
      (node (ref "D15") (pin "3") (pinfunction "GA_3") (pintype "passive"))
      (node (ref "D15") (pin "5") (pinfunction "RA_5") (pintype "passive"))
      (node (ref "D16") (pin "1") (pinfunction "BA_1") (pintype "passive"))
      (node (ref "D16") (pin "3") (pinfunction "GA_3") (pintype "passive"))
      (node (ref "D16") (pin "5") (pinfunction "RA_5") (pintype "passive"))
      (node (ref "D17") (pin "1") (pinfunction "BA_1") (pintype "passive"))
      (node (ref "D17") (pin "3") (pinfunction "GA_3") (pintype "passive"))
      (node (ref "D17") (pin "5") (pinfunction "RA_5") (pintype "passive"))
      (node (ref "D18") (pin "1") (pinfunction "BA_1") (pintype "passive"))
      (node (ref "D18") (pin "3") (pinfunction "GA_3") (pintype "passive"))
      (node (ref "D18") (pin "5") (pinfunction "RA_5") (pintype "passive"))
      (node (ref "D19") (pin "1") (pinfunction "BA_1") (pintype "passive"))
      (node (ref "D19") (pin "3") (pinfunction "GA_3") (pintype "passive"))
      (node (ref "D19") (pin "5") (pinfunction "RA_5") (pintype "passive"))
      (node (ref "D2") (pin "1") (pinfunction "BA_1") (pintype "passive"))
      (node (ref "D2") (pin "3") (pinfunction "GA_3") (pintype "passive"))
      (node (ref "D2") (pin "5") (pinfunction "RA_5") (pintype "passive"))
      (node (ref "D20") (pin "1") (pinfunction "BA_1") (pintype "passive"))
      (node (ref "D20") (pin "3") (pinfunction "GA_3") (pintype "passive"))
      (node (ref "D20") (pin "5") (pinfunction "RA_5") (pintype "passive"))
      (node (ref "D21") (pin "1") (pinfunction "BA_1") (pintype "passive"))
      (node (ref "D21") (pin "3") (pinfunction "GA_3") (pintype "passive"))
      (node (ref "D21") (pin "5") (pinfunction "RA_5") (pintype "passive"))
      (node (ref "D3") (pin "1") (pinfunction "BA_1") (pintype "passive"))
      (node (ref "D3") (pin "3") (pinfunction "GA_3") (pintype "passive"))
      (node (ref "D3") (pin "5") (pinfunction "RA_5") (pintype "passive"))
      (node (ref "D4") (pin "1") (pinfunction "BA_1") (pintype "passive"))
      (node (ref "D4") (pin "3") (pinfunction "GA_3") (pintype "passive"))
      (node (ref "D4") (pin "5") (pinfunction "RA_5") (pintype "passive"))
      (node (ref "D5") (pin "1") (pinfunction "BA_1") (pintype "passive"))
      (node (ref "D5") (pin "3") (pinfunction "GA_3") (pintype "passive"))
      (node (ref "D5") (pin "5") (pinfunction "RA_5") (pintype "passive"))
      (node (ref "D6") (pin "1") (pinfunction "BA_1") (pintype "passive"))
      (node (ref "D6") (pin "3") (pinfunction "GA_3") (pintype "passive"))
      (node (ref "D6") (pin "5") (pinfunction "RA_5") (pintype "passive"))
      (node (ref "D7") (pin "1") (pinfunction "BA_1") (pintype "passive"))
      (node (ref "D7") (pin "3") (pinfunction "GA_3") (pintype "passive"))
      (node (ref "D7") (pin "5") (pinfunction "RA_5") (pintype "passive"))
      (node (ref "D8") (pin "1") (pinfunction "BA_1") (pintype "passive"))
      (node (ref "D8") (pin "3") (pinfunction "GA_3") (pintype "passive"))
      (node (ref "D8") (pin "5") (pinfunction "RA_5") (pintype "passive"))
      (node (ref "D9") (pin "1") (pinfunction "BA_1") (pintype "passive"))
      (node (ref "D9") (pin "3") (pinfunction "GA_3") (pintype "passive"))
      (node (ref "D9") (pin "5") (pinfunction "RA_5") (pintype "passive"))
      (node (ref "J1") (pin "1") (pinfunction "5V_1") (pintype "power_in"))
      (node (ref "U2") (pin "1") (pinfunction "VI_1") (pintype "passive"))
      (node (ref "U2") (pin "3") (pinfunction "EN_3") (pintype "passive"))
    )
    (net (code "13") (name "GND") (class "Default")
      (node (ref "C1") (pin "1") (pinfunction "1_1") (pintype "passive"))
      (node (ref "C2") (pin "1") (pinfunction "1_1") (pintype "passive"))
      (node (ref "J1") (pin "0") (pinfunction "SH_0") (pintype "passive"))
      (node (ref "J1") (pin "5") (pinfunction "GND_5") (pintype "power_in"))
      (node (ref "J2") (pin "4") (pinfunction "4_4") (pintype "passive"))
      (node (ref "J3") (pin "0") (pinfunction "PIN_0") (pintype "passive"))
      (node (ref "J4") (pin "0") (pinfunction "PIN_0") (pintype "passive"))
      (node (ref "J5") (pin "0") (pinfunction "PIN_0") (pintype "passive"))
      (node (ref "J6") (pin "3") (pinfunction "3_3") (pintype "passive"))
      (node (ref "Q1") (pin "3") (pinfunction "S_3") (pintype "passive"))
      (node (ref "Q2") (pin "3") (pinfunction "S_3") (pintype "passive"))
      (node (ref "Q3") (pin "3") (pinfunction "S_3") (pintype "passive"))
      (node (ref "SW1") (pin "3") (pinfunction "3_3") (pintype "passive"))
      (node (ref "SW1") (pin "4") (pinfunction "4_4") (pintype "passive"))
      (node (ref "U1") (pin "13") (pinfunction "GND_13") (pintype "passive"))
      (node (ref "U1") (pin "18") (pinfunction "GND_18") (pintype "passive"))
      (node (ref "U1") (pin "19") (pinfunction "GND_19") (pintype "passive"))
      (node (ref "U1") (pin "9") (pinfunction "GND_9") (pintype "passive"))
      (node (ref "U2") (pin "2") (pinfunction "GND_2") (pintype "passive"))
    )
    (net (code "14") (name "Net-(D1-BK)") (class "Default")
      (node (ref "D1") (pin "2") (pinfunction "BK_2") (pintype "passive"))
      (node (ref "R3") (pin "1") (pinfunction "1_1") (pintype "passive"))
    )
    (net (code "15") (name "Net-(D1-GK)") (class "Default")
      (node (ref "D1") (pin "4") (pinfunction "GK_4") (pintype "passive"))
      (node (ref "R2") (pin "1") (pinfunction "1_1") (pintype "passive"))
    )
    (net (code "16") (name "Net-(D1-RK)") (class "Default")
      (node (ref "D1") (pin "6") (pinfunction "RK_6") (pintype "passive"))
      (node (ref "R1") (pin "1") (pinfunction "1_1") (pintype "passive"))
    )
    (net (code "17") (name "Net-(D2-BK)") (class "Default")
      (node (ref "D2") (pin "2") (pinfunction "BK_2") (pintype "passive"))
      (node (ref "R6") (pin "1") (pinfunction "1_1") (pintype "passive"))
    )
    (net (code "18") (name "Net-(D2-GK)") (class "Default")
      (node (ref "D2") (pin "4") (pinfunction "GK_4") (pintype "passive"))
      (node (ref "R5") (pin "1") (pinfunction "1_1") (pintype "passive"))
    )
    (net (code "19") (name "Net-(D2-RK)") (class "Default")
      (node (ref "D2") (pin "6") (pinfunction "RK_6") (pintype "passive"))
      (node (ref "R4") (pin "1") (pinfunction "1_1") (pintype "passive"))
    )
    (net (code "20") (name "Net-(D3-BK)") (class "Default")
      (node (ref "D3") (pin "2") (pinfunction "BK_2") (pintype "passive"))
      (node (ref "R9") (pin "1") (pinfunction "1_1") (pintype "passive"))
    )
    (net (code "21") (name "Net-(D3-GK)") (class "Default")
      (node (ref "D3") (pin "4") (pinfunction "GK_4") (pintype "passive"))
      (node (ref "R8") (pin "1") (pinfunction "1_1") (pintype "passive"))
    )
    (net (code "22") (name "Net-(D3-RK)") (class "Default")
      (node (ref "D3") (pin "6") (pinfunction "RK_6") (pintype "passive"))
      (node (ref "R7") (pin "1") (pinfunction "1_1") (pintype "passive"))
    )
    (net (code "23") (name "Net-(D4-BK)") (class "Default")
      (node (ref "D4") (pin "2") (pinfunction "BK_2") (pintype "passive"))
      (node (ref "R12") (pin "1") (pinfunction "1_1") (pintype "passive"))
    )
    (net (code "24") (name "Net-(D4-GK)") (class "Default")
      (node (ref "D4") (pin "4") (pinfunction "GK_4") (pintype "passive"))
      (node (ref "R11") (pin "1") (pinfunction "1_1") (pintype "passive"))
    )
    (net (code "25") (name "Net-(D4-RK)") (class "Default")
      (node (ref "D4") (pin "6") (pinfunction "RK_6") (pintype "passive"))
      (node (ref "R10") (pin "1") (pinfunction "1_1") (pintype "passive"))
    )
    (net (code "26") (name "Net-(D5-BK)") (class "Default")
      (node (ref "D5") (pin "2") (pinfunction "BK_2") (pintype "passive"))
      (node (ref "R15") (pin "1") (pinfunction "1_1") (pintype "passive"))
    )
    (net (code "27") (name "Net-(D5-GK)") (class "Default")
      (node (ref "D5") (pin "4") (pinfunction "GK_4") (pintype "passive"))
      (node (ref "R14") (pin "1") (pinfunction "1_1") (pintype "passive"))
    )
    (net (code "28") (name "Net-(D5-RK)") (class "Default")
      (node (ref "D5") (pin "6") (pinfunction "RK_6") (pintype "passive"))
      (node (ref "R13") (pin "1") (pinfunction "1_1") (pintype "passive"))
    )
    (net (code "29") (name "Net-(D6-BK)") (class "Default")
      (node (ref "D6") (pin "2") (pinfunction "BK_2") (pintype "passive"))
      (node (ref "R18") (pin "1") (pinfunction "1_1") (pintype "passive"))
    )
    (net (code "30") (name "Net-(D6-GK)") (class "Default")
      (node (ref "D6") (pin "4") (pinfunction "GK_4") (pintype "passive"))
      (node (ref "R17") (pin "1") (pinfunction "1_1") (pintype "passive"))
    )
    (net (code "31") (name "Net-(D6-RK)") (class "Default")
      (node (ref "D6") (pin "6") (pinfunction "RK_6") (pintype "passive"))
      (node (ref "R16") (pin "1") (pinfunction "1_1") (pintype "passive"))
    )
    (net (code "32") (name "Net-(D7-BK)") (class "Default")
      (node (ref "D7") (pin "2") (pinfunction "BK_2") (pintype "passive"))
      (node (ref "R21") (pin "1") (pinfunction "1_1") (pintype "passive"))
    )
    (net (code "33") (name "Net-(D7-GK)") (class "Default")
      (node (ref "D7") (pin "4") (pinfunction "GK_4") (pintype "passive"))
      (node (ref "R20") (pin "1") (pinfunction "1_1") (pintype "passive"))
    )
    (net (code "34") (name "Net-(D7-RK)") (class "Default")
      (node (ref "D7") (pin "6") (pinfunction "RK_6") (pintype "passive"))
      (node (ref "R19") (pin "1") (pinfunction "1_1") (pintype "passive"))
    )
    (net (code "35") (name "Net-(D8-BK)") (class "Default")
      (node (ref "D8") (pin "2") (pinfunction "BK_2") (pintype "passive"))
      (node (ref "R24") (pin "1") (pinfunction "1_1") (pintype "passive"))
    )
    (net (code "36") (name "Net-(D8-GK)") (class "Default")
      (node (ref "D8") (pin "4") (pinfunction "GK_4") (pintype "passive"))
      (node (ref "R23") (pin "1") (pinfunction "1_1") (pintype "passive"))
    )
    (net (code "37") (name "Net-(D8-RK)") (class "Default")
      (node (ref "D8") (pin "6") (pinfunction "RK_6") (pintype "passive"))
      (node (ref "R22") (pin "1") (pinfunction "1_1") (pintype "passive"))
    )
    (net (code "38") (name "Net-(D9-BK)") (class "Default")
      (node (ref "D9") (pin "2") (pinfunction "BK_2") (pintype "passive"))
      (node (ref "R27") (pin "1") (pinfunction "1_1") (pintype "passive"))
    )
    (net (code "39") (name "Net-(D9-GK)") (class "Default")
      (node (ref "D9") (pin "4") (pinfunction "GK_4") (pintype "passive"))
      (node (ref "R26") (pin "1") (pinfunction "1_1") (pintype "passive"))
    )
    (net (code "40") (name "Net-(D9-RK)") (class "Default")
      (node (ref "D9") (pin "6") (pinfunction "RK_6") (pintype "passive"))
      (node (ref "R25") (pin "1") (pinfunction "1_1") (pintype "passive"))
    )
    (net (code "41") (name "Net-(D10-BK)") (class "Default")
      (node (ref "D10") (pin "2") (pinfunction "BK_2") (pintype "passive"))
      (node (ref "R30") (pin "1") (pinfunction "1_1") (pintype "passive"))
    )
    (net (code "42") (name "Net-(D10-GK)") (class "Default")
      (node (ref "D10") (pin "4") (pinfunction "GK_4") (pintype "passive"))
      (node (ref "R29") (pin "1") (pinfunction "1_1") (pintype "passive"))
    )
    (net (code "43") (name "Net-(D10-RK)") (class "Default")
      (node (ref "D10") (pin "6") (pinfunction "RK_6") (pintype "passive"))
      (node (ref "R28") (pin "1") (pinfunction "1_1") (pintype "passive"))
    )
    (net (code "44") (name "Net-(D11-BK)") (class "Default")
      (node (ref "D11") (pin "2") (pinfunction "BK_2") (pintype "passive"))
      (node (ref "R33") (pin "1") (pinfunction "1_1") (pintype "passive"))
    )
    (net (code "45") (name "Net-(D11-GK)") (class "Default")
      (node (ref "D11") (pin "4") (pinfunction "GK_4") (pintype "passive"))
      (node (ref "R32") (pin "1") (pinfunction "1_1") (pintype "passive"))
    )
    (net (code "46") (name "Net-(D11-RK)") (class "Default")
      (node (ref "D11") (pin "6") (pinfunction "RK_6") (pintype "passive"))
      (node (ref "R31") (pin "1") (pinfunction "1_1") (pintype "passive"))
    )
    (net (code "47") (name "Net-(D12-BK)") (class "Default")
      (node (ref "D12") (pin "2") (pinfunction "BK_2") (pintype "passive"))
      (node (ref "R36") (pin "1") (pinfunction "1_1") (pintype "passive"))
    )
    (net (code "48") (name "Net-(D12-GK)") (class "Default")
      (node (ref "D12") (pin "4") (pinfunction "GK_4") (pintype "passive"))
      (node (ref "R35") (pin "1") (pinfunction "1_1") (pintype "passive"))
    )
    (net (code "49") (name "Net-(D12-RK)") (class "Default")
      (node (ref "D12") (pin "6") (pinfunction "RK_6") (pintype "passive"))
      (node (ref "R34") (pin "1") (pinfunction "1_1") (pintype "passive"))
    )
    (net (code "50") (name "Net-(D13-BK)") (class "Default")
      (node (ref "D13") (pin "2") (pinfunction "BK_2") (pintype "passive"))
      (node (ref "R39") (pin "1") (pinfunction "1_1") (pintype "passive"))
    )
    (net (code "51") (name "Net-(D13-GK)") (class "Default")
      (node (ref "D13") (pin "4") (pinfunction "GK_4") (pintype "passive"))
      (node (ref "R38") (pin "1") (pinfunction "1_1") (pintype "passive"))
    )
    (net (code "52") (name "Net-(D13-RK)") (class "Default")
      (node (ref "D13") (pin "6") (pinfunction "RK_6") (pintype "passive"))
      (node (ref "R37") (pin "1") (pinfunction "1_1") (pintype "passive"))
    )
    (net (code "53") (name "Net-(D14-BK)") (class "Default")
      (node (ref "D14") (pin "2") (pinfunction "BK_2") (pintype "passive"))
      (node (ref "R42") (pin "1") (pinfunction "1_1") (pintype "passive"))
    )
    (net (code "54") (name "Net-(D14-GK)") (class "Default")
      (node (ref "D14") (pin "4") (pinfunction "GK_4") (pintype "passive"))
      (node (ref "R41") (pin "1") (pinfunction "1_1") (pintype "passive"))
    )
    (net (code "55") (name "Net-(D14-RK)") (class "Default")
      (node (ref "D14") (pin "6") (pinfunction "RK_6") (pintype "passive"))
      (node (ref "R40") (pin "1") (pinfunction "1_1") (pintype "passive"))
    )
    (net (code "56") (name "Net-(D15-BK)") (class "Default")
      (node (ref "D15") (pin "2") (pinfunction "BK_2") (pintype "passive"))
      (node (ref "R45") (pin "1") (pinfunction "1_1") (pintype "passive"))
    )
    (net (code "57") (name "Net-(D15-GK)") (class "Default")
      (node (ref "D15") (pin "4") (pinfunction "GK_4") (pintype "passive"))
      (node (ref "R44") (pin "1") (pinfunction "1_1") (pintype "passive"))
    )
    (net (code "58") (name "Net-(D15-RK)") (class "Default")
      (node (ref "D15") (pin "6") (pinfunction "RK_6") (pintype "passive"))
      (node (ref "R43") (pin "1") (pinfunction "1_1") (pintype "passive"))
    )
    (net (code "59") (name "Net-(D16-BK)") (class "Default")
      (node (ref "D16") (pin "2") (pinfunction "BK_2") (pintype "passive"))
      (node (ref "R48") (pin "1") (pinfunction "1_1") (pintype "passive"))
    )
    (net (code "60") (name "Net-(D16-GK)") (class "Default")
      (node (ref "D16") (pin "4") (pinfunction "GK_4") (pintype "passive"))
      (node (ref "R47") (pin "1") (pinfunction "1_1") (pintype "passive"))
    )
    (net (code "61") (name "Net-(D16-RK)") (class "Default")
      (node (ref "D16") (pin "6") (pinfunction "RK_6") (pintype "passive"))
      (node (ref "R46") (pin "1") (pinfunction "1_1") (pintype "passive"))
    )
    (net (code "62") (name "Net-(D17-BK)") (class "Default")
      (node (ref "D17") (pin "2") (pinfunction "BK_2") (pintype "passive"))
      (node (ref "R51") (pin "1") (pinfunction "1_1") (pintype "passive"))
    )
    (net (code "63") (name "Net-(D17-GK)") (class "Default")
      (node (ref "D17") (pin "4") (pinfunction "GK_4") (pintype "passive"))
      (node (ref "R50") (pin "1") (pinfunction "1_1") (pintype "passive"))
    )
    (net (code "64") (name "Net-(D17-RK)") (class "Default")
      (node (ref "D17") (pin "6") (pinfunction "RK_6") (pintype "passive"))
      (node (ref "R49") (pin "1") (pinfunction "1_1") (pintype "passive"))
    )
    (net (code "65") (name "Net-(D18-BK)") (class "Default")
      (node (ref "D18") (pin "2") (pinfunction "BK_2") (pintype "passive"))
      (node (ref "R54") (pin "1") (pinfunction "1_1") (pintype "passive"))
    )
    (net (code "66") (name "Net-(D18-GK)") (class "Default")
      (node (ref "D18") (pin "4") (pinfunction "GK_4") (pintype "passive"))
      (node (ref "R53") (pin "1") (pinfunction "1_1") (pintype "passive"))
    )
    (net (code "67") (name "Net-(D18-RK)") (class "Default")
      (node (ref "D18") (pin "6") (pinfunction "RK_6") (pintype "passive"))
      (node (ref "R52") (pin "1") (pinfunction "1_1") (pintype "passive"))
    )
    (net (code "68") (name "Net-(D19-BK)") (class "Default")
      (node (ref "D19") (pin "2") (pinfunction "BK_2") (pintype "passive"))
      (node (ref "R57") (pin "1") (pinfunction "1_1") (pintype "passive"))
    )
    (net (code "69") (name "Net-(D19-GK)") (class "Default")
      (node (ref "D19") (pin "4") (pinfunction "GK_4") (pintype "passive"))
      (node (ref "R56") (pin "1") (pinfunction "1_1") (pintype "passive"))
    )
    (net (code "70") (name "Net-(D19-RK)") (class "Default")
      (node (ref "D19") (pin "6") (pinfunction "RK_6") (pintype "passive"))
      (node (ref "R55") (pin "1") (pinfunction "1_1") (pintype "passive"))
    )
    (net (code "71") (name "Net-(D20-BK)") (class "Default")
      (node (ref "D20") (pin "2") (pinfunction "BK_2") (pintype "passive"))
      (node (ref "R60") (pin "1") (pinfunction "1_1") (pintype "passive"))
    )
    (net (code "72") (name "Net-(D20-GK)") (class "Default")
      (node (ref "D20") (pin "4") (pinfunction "GK_4") (pintype "passive"))
      (node (ref "R59") (pin "1") (pinfunction "1_1") (pintype "passive"))
    )
    (net (code "73") (name "Net-(D20-RK)") (class "Default")
      (node (ref "D20") (pin "6") (pinfunction "RK_6") (pintype "passive"))
      (node (ref "R58") (pin "1") (pinfunction "1_1") (pintype "passive"))
    )
    (net (code "74") (name "Net-(D21-BK)") (class "Default")
      (node (ref "D21") (pin "2") (pinfunction "BK_2") (pintype "passive"))
      (node (ref "R63") (pin "1") (pinfunction "1_1") (pintype "passive"))
    )
    (net (code "75") (name "Net-(D21-GK)") (class "Default")
      (node (ref "D21") (pin "4") (pinfunction "GK_4") (pintype "passive"))
      (node (ref "R62") (pin "1") (pinfunction "1_1") (pintype "passive"))
    )
    (net (code "76") (name "Net-(D21-RK)") (class "Default")
      (node (ref "D21") (pin "6") (pinfunction "RK_6") (pintype "passive"))
      (node (ref "R61") (pin "1") (pinfunction "1_1") (pintype "passive"))
    )
    (net (code "77") (name "Net-(Q1-G)") (class "Default")
      (node (ref "Q1") (pin "1") (pinfunction "G_1") (pintype "passive"))
      (node (ref "R64") (pin "2") (pinfunction "2_2") (pintype "passive"))
    )
    (net (code "78") (name "Net-(Q2-G)") (class "Default")
      (node (ref "Q2") (pin "1") (pinfunction "G_1") (pintype "passive"))
      (node (ref "R65") (pin "2") (pinfunction "2_2") (pintype "passive"))
    )
    (net (code "79") (name "Net-(Q3-G)") (class "Default")
      (node (ref "Q3") (pin "1") (pinfunction "G_1") (pintype "passive"))
      (node (ref "R67") (pin "2") (pinfunction "2_2") (pintype "passive"))
    )
    (net (code "80") (name "Net-(U1-IO0)") (class "Default")
      (node (ref "R66") (pin "1") (pinfunction "1_1") (pintype "passive"))
      (node (ref "SW1") (pin "1") (pinfunction "1_1") (pintype "passive"))
      (node (ref "SW1") (pin "2") (pinfunction "2_2") (pintype "passive"))
      (node (ref "U1") (pin "8") (pinfunction "IO0_8") (pintype "passive"))
    )
    (net (code "81") (name "Net-(U2-SW)") (class "Default")
      (node (ref "L1") (pin "1") (pinfunction "1_1") (pintype "passive"))
      (node (ref "U2") (pin "5") (pinfunction "SW_5") (pintype "passive"))
    )
    (net (code "82") (name "unconnected-(J1-D+-Pad3)") (class "Default")
      (node (ref "J1") (pin "3") (pinfunction "D+_3") (pintype "bidirectional+no_connect"))
    )
    (net (code "83") (name "unconnected-(J1-D--Pad2)") (class "Default")
      (node (ref "J1") (pin "2") (pinfunction "D-_2") (pintype "bidirectional+no_connect"))
    )
    (net (code "84") (name "unconnected-(J1-ID-Pad4)") (class "Default")
      (node (ref "J1") (pin "4") (pinfunction "ID_4") (pintype "passive+no_connect"))
    )
    (net (code "85") (name "unconnected-(U1-IO2-Pad7)") (class "Default")
      (node (ref "U1") (pin "7") (pinfunction "IO2_7") (pintype "passive+no_connect"))
    )
    (net (code "86") (name "unconnected-(U1-IO4-Pad10)") (class "Default")
      (node (ref "U1") (pin "10") (pinfunction "IO4_10") (pintype "passive+no_connect"))
    )
    (net (code "87") (name "unconnected-(U1-IO5-Pad14)") (class "Default")
      (node (ref "U1") (pin "14") (pinfunction "IO5_14") (pintype "passive+no_connect"))
    )
    (net (code "88") (name "unconnected-(U1-IO16-Pad17)") (class "Default")
      (node (ref "U1") (pin "17") (pinfunction "IO16_17") (pintype "passive+no_connect"))
    )
    (net (code "89") (name "unconnected-(U1-TOUT-Pad16)") (class "Default")
      (node (ref "U1") (pin "16") (pinfunction "TOUT_16") (pintype "passive+no_connect"))
    )
  )
)
